# Hazard_Beacon_Timer.net
KiCad netlist of a schematic drawn in EAGLE
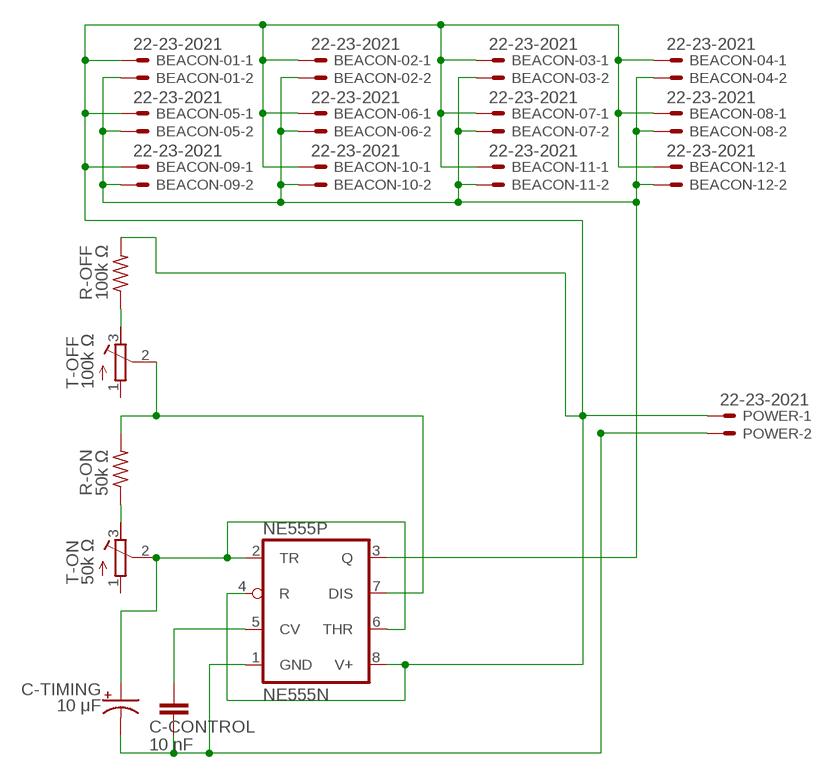
[diagram p0: schematic, sheet 1]

(export (version "E")
  (design (tool "Eeschema 10.0.6"))
  (components
    (comp (ref "BEACON-01")
      (value "22-23-2021")
      (footprint "eagle-import:22-23-2021")
      (fields (field (name "MF") "MOLEX"))
      (libsource (lib "eagle-import") (part "22-23-2021"))
    )
    (comp (ref "BEACON-02")
      (value "22-23-2021")
      (footprint "eagle-import:22-23-2021")
      (fields (field (name "MF") "MOLEX"))
      (libsource (lib "eagle-import") (part "22-23-2021"))
    )
    (comp (ref "BEACON-03")
      (value "22-23-2021")
      (footprint "eagle-import:22-23-2021")
      (fields (field (name "MF") "MOLEX"))
      (libsource (lib "eagle-import") (part "22-23-2021"))
    )
    (comp (ref "BEACON-04")
      (value "22-23-2021")
      (footprint "eagle-import:22-23-2021")
      (fields (field (name "MF") "MOLEX"))
      (libsource (lib "eagle-import") (part "22-23-2021"))
    )
    (comp (ref "BEACON-05")
      (value "22-23-2021")
      (footprint "eagle-import:22-23-2021")
      (fields (field (name "MF") "MOLEX"))
      (libsource (lib "eagle-import") (part "22-23-2021"))
    )
    (comp (ref "BEACON-06")
      (value "22-23-2021")
      (footprint "eagle-import:22-23-2021")
      (fields (field (name "MF") "MOLEX"))
      (libsource (lib "eagle-import") (part "22-23-2021"))
    )
    (comp (ref "BEACON-07")
      (value "22-23-2021")
      (footprint "eagle-import:22-23-2021")
      (fields (field (name "MF") "MOLEX"))
      (libsource (lib "eagle-import") (part "22-23-2021"))
    )
    (comp (ref "BEACON-08")
      (value "22-23-2021")
      (footprint "eagle-import:22-23-2021")
      (fields (field (name "MF") "MOLEX"))
      (libsource (lib "eagle-import") (part "22-23-2021"))
    )
    (comp (ref "BEACON-09")
      (value "22-23-2021")
      (footprint "eagle-import:22-23-2021")
      (fields (field (name "MF") "MOLEX"))
      (libsource (lib "eagle-import") (part "22-23-2021"))
    )
    (comp (ref "BEACON-10")
      (value "22-23-2021")
      (footprint "eagle-import:22-23-2021")
      (fields (field (name "MF") "MOLEX"))
      (libsource (lib "eagle-import") (part "22-23-2021"))
    )
    (comp (ref "BEACON-11")
      (value "22-23-2021")
      (footprint "eagle-import:22-23-2021")
      (fields (field (name "MF") "MOLEX"))
      (libsource (lib "eagle-import") (part "22-23-2021"))
    )
    (comp (ref "BEACON-12")
      (value "22-23-2021")
      (footprint "eagle-import:22-23-2021")
      (fields (field (name "MF") "MOLEX"))
      (libsource (lib "eagle-import") (part "22-23-2021"))
    )
    (comp (ref "C-CONTROL")
      (value "10 nF")
      (footprint "eagle-import:C2.5-2")
      (libsource (lib "eagle-import") (part "C2.5/2"))
    )
    (comp (ref "C-TIMING")
      (value "10 μF")
      (footprint "eagle-import:E2-5")
      (libsource (lib "eagle-import") (part "CPOL-USE2-5"))
    )
    (comp (ref "NE555P")
      (value "NE555N")
      (footprint "eagle-import:DIL08")
      (libsource (lib "eagle-import") (part "555NNE"))
    )
    (comp (ref "POWER")
      (value "22-23-2021")
      (footprint "eagle-import:22-23-2021")
      (fields (field (name "MF") "MOLEX"))
      (libsource (lib "eagle-import") (part "22-23-2021"))
    )
    (comp (ref "R-OFF")
      (value "100k Ω")
      (footprint "eagle-import:0207_7")
      (libsource (lib "eagle-import") (part "R-US_0207/7"))
    )
    (comp (ref "R-ON")
      (value "50k Ω")
      (footprint "eagle-import:0207_7")
      (libsource (lib "eagle-import") (part "R-US_0207/7"))
    )
    (comp (ref "T-OFF")
      (value "100k Ω")
      (footprint "eagle-import:RTRIM5X")
      (libsource (lib "eagle-import") (part "R-TRIMM5X"))
    )
    (comp (ref "T-ON")
      (value "50k Ω")
      (footprint "eagle-import:RTRIM5X")
      (libsource (lib "eagle-import") (part "R-TRIMM5X"))
    )
  )
  (nets
    (net (code "1") (name "Net-(BEACON-01A-S)") (class "Default")
      (node (ref "BEACON-01") (pin "1") (pinfunction "S_1") (pintype "passive"))
      (node (ref "BEACON-02") (pin "1") (pinfunction "S_1") (pintype "passive"))
      (node (ref "BEACON-03") (pin "1") (pinfunction "S_1") (pintype "passive"))
      (node (ref "BEACON-04") (pin "1") (pinfunction "S_1") (pintype "passive"))
      (node (ref "BEACON-05") (pin "1") (pinfunction "S_1") (pintype "passive"))
      (node (ref "BEACON-06") (pin "1") (pinfunction "S_1") (pintype "passive"))
      (node (ref "BEACON-07") (pin "1") (pinfunction "S_1") (pintype "passive"))
      (node (ref "BEACON-08") (pin "1") (pinfunction "S_1") (pintype "passive"))
      (node (ref "BEACON-09") (pin "1") (pinfunction "S_1") (pintype "passive"))
      (node (ref "BEACON-10") (pin "1") (pinfunction "S_1") (pintype "passive"))
      (node (ref "BEACON-11") (pin "1") (pinfunction "S_1") (pintype "passive"))
      (node (ref "BEACON-12") (pin "1") (pinfunction "S_1") (pintype "passive"))
      (node (ref "NE555P") (pin "4") (pinfunction "R_4") (pintype "input"))
      (node (ref "NE555P") (pin "8") (pinfunction "V+_8") (pintype "power_in"))
      (node (ref "POWER") (pin "1") (pinfunction "S_1") (pintype "passive"))
      (node (ref "R-OFF") (pin "2") (pinfunction "2_2") (pintype "passive"))
    )
    (net (code "2") (name "Net-(BEACON-01B-S)") (class "Default")
      (node (ref "BEACON-01") (pin "2") (pinfunction "S_2") (pintype "passive"))
      (node (ref "BEACON-02") (pin "2") (pinfunction "S_2") (pintype "passive"))
      (node (ref "BEACON-03") (pin "2") (pinfunction "S_2") (pintype "passive"))
      (node (ref "BEACON-04") (pin "2") (pinfunction "S_2") (pintype "passive"))
      (node (ref "BEACON-05") (pin "2") (pinfunction "S_2") (pintype "passive"))
      (node (ref "BEACON-06") (pin "2") (pinfunction "S_2") (pintype "passive"))
      (node (ref "BEACON-07") (pin "2") (pinfunction "S_2") (pintype "passive"))
      (node (ref "BEACON-08") (pin "2") (pinfunction "S_2") (pintype "passive"))
      (node (ref "BEACON-09") (pin "2") (pinfunction "S_2") (pintype "passive"))
      (node (ref "BEACON-10") (pin "2") (pinfunction "S_2") (pintype "passive"))
      (node (ref "BEACON-11") (pin "2") (pinfunction "S_2") (pintype "passive"))
      (node (ref "BEACON-12") (pin "2") (pinfunction "S_2") (pintype "passive"))
      (node (ref "NE555P") (pin "3") (pinfunction "Q_3") (pintype "output"))
    )
    (net (code "3") (name "Net-(NE555P-CV)") (class "Default")
      (node (ref "C-CONTROL") (pin "1") (pinfunction "1_1") (pintype "passive"))
      (node (ref "NE555P") (pin "5") (pinfunction "CV_5") (pintype "input"))
    )
    (net (code "4") (name "Net-(NE555P-DIS)") (class "Default")
      (node (ref "NE555P") (pin "7") (pinfunction "DIS_7") (pintype "input"))
      (node (ref "R-ON") (pin "2") (pinfunction "2_2") (pintype "passive"))
      (node (ref "T-OFF") (pin "2") (pinfunction "S_2") (pintype "passive"))
    )
    (net (code "5") (name "Net-(NE555P-GND)") (class "Default")
      (node (ref "C-CONTROL") (pin "2") (pinfunction "2_2") (pintype "passive"))
      (node (ref "C-TIMING") (pin "-") (pinfunction "-_-") (pintype "passive"))
      (node (ref "NE555P") (pin "1") (pinfunction "GND_1") (pintype "power_in"))
      (node (ref "POWER") (pin "2") (pinfunction "S_2") (pintype "passive"))
    )
    (net (code "6") (name "Net-(NE555P-THR)") (class "Default")
      (node (ref "C-TIMING") (pin "+") (pinfunction "+_+") (pintype "passive"))
      (node (ref "NE555P") (pin "2") (pinfunction "TR_2") (pintype "input"))
      (node (ref "NE555P") (pin "6") (pinfunction "THR_6") (pintype "input"))
      (node (ref "T-ON") (pin "2") (pinfunction "S_2") (pintype "passive"))
    )
    (net (code "7") (name "Net-(T-OFF-E)") (class "Default")
      (node (ref "R-OFF") (pin "1") (pinfunction "1_1") (pintype "passive"))
      (node (ref "T-OFF") (pin "3") (pinfunction "E_3") (pintype "passive"))
    )
    (net (code "8") (name "Net-(T-ON-E)") (class "Default")
      (node (ref "R-ON") (pin "1") (pinfunction "1_1") (pintype "passive"))
      (node (ref "T-ON") (pin "3") (pinfunction "E_3") (pintype "passive"))
    )
    (net (code "9") (name "unconnected-(T-OFF-A-Pad1)") (class "Default")
      (node (ref "T-OFF") (pin "1") (pinfunction "A_1") (pintype "passive"))
    )
    (net (code "10") (name "unconnected-(T-ON-A-Pad1)") (class "Default")
      (node (ref "T-ON") (pin "1") (pinfunction "A_1") (pintype "passive"))
    )
  )
)
